# spectral_clock.net
KiCad netlist of a schematic drawn in Altium Designer
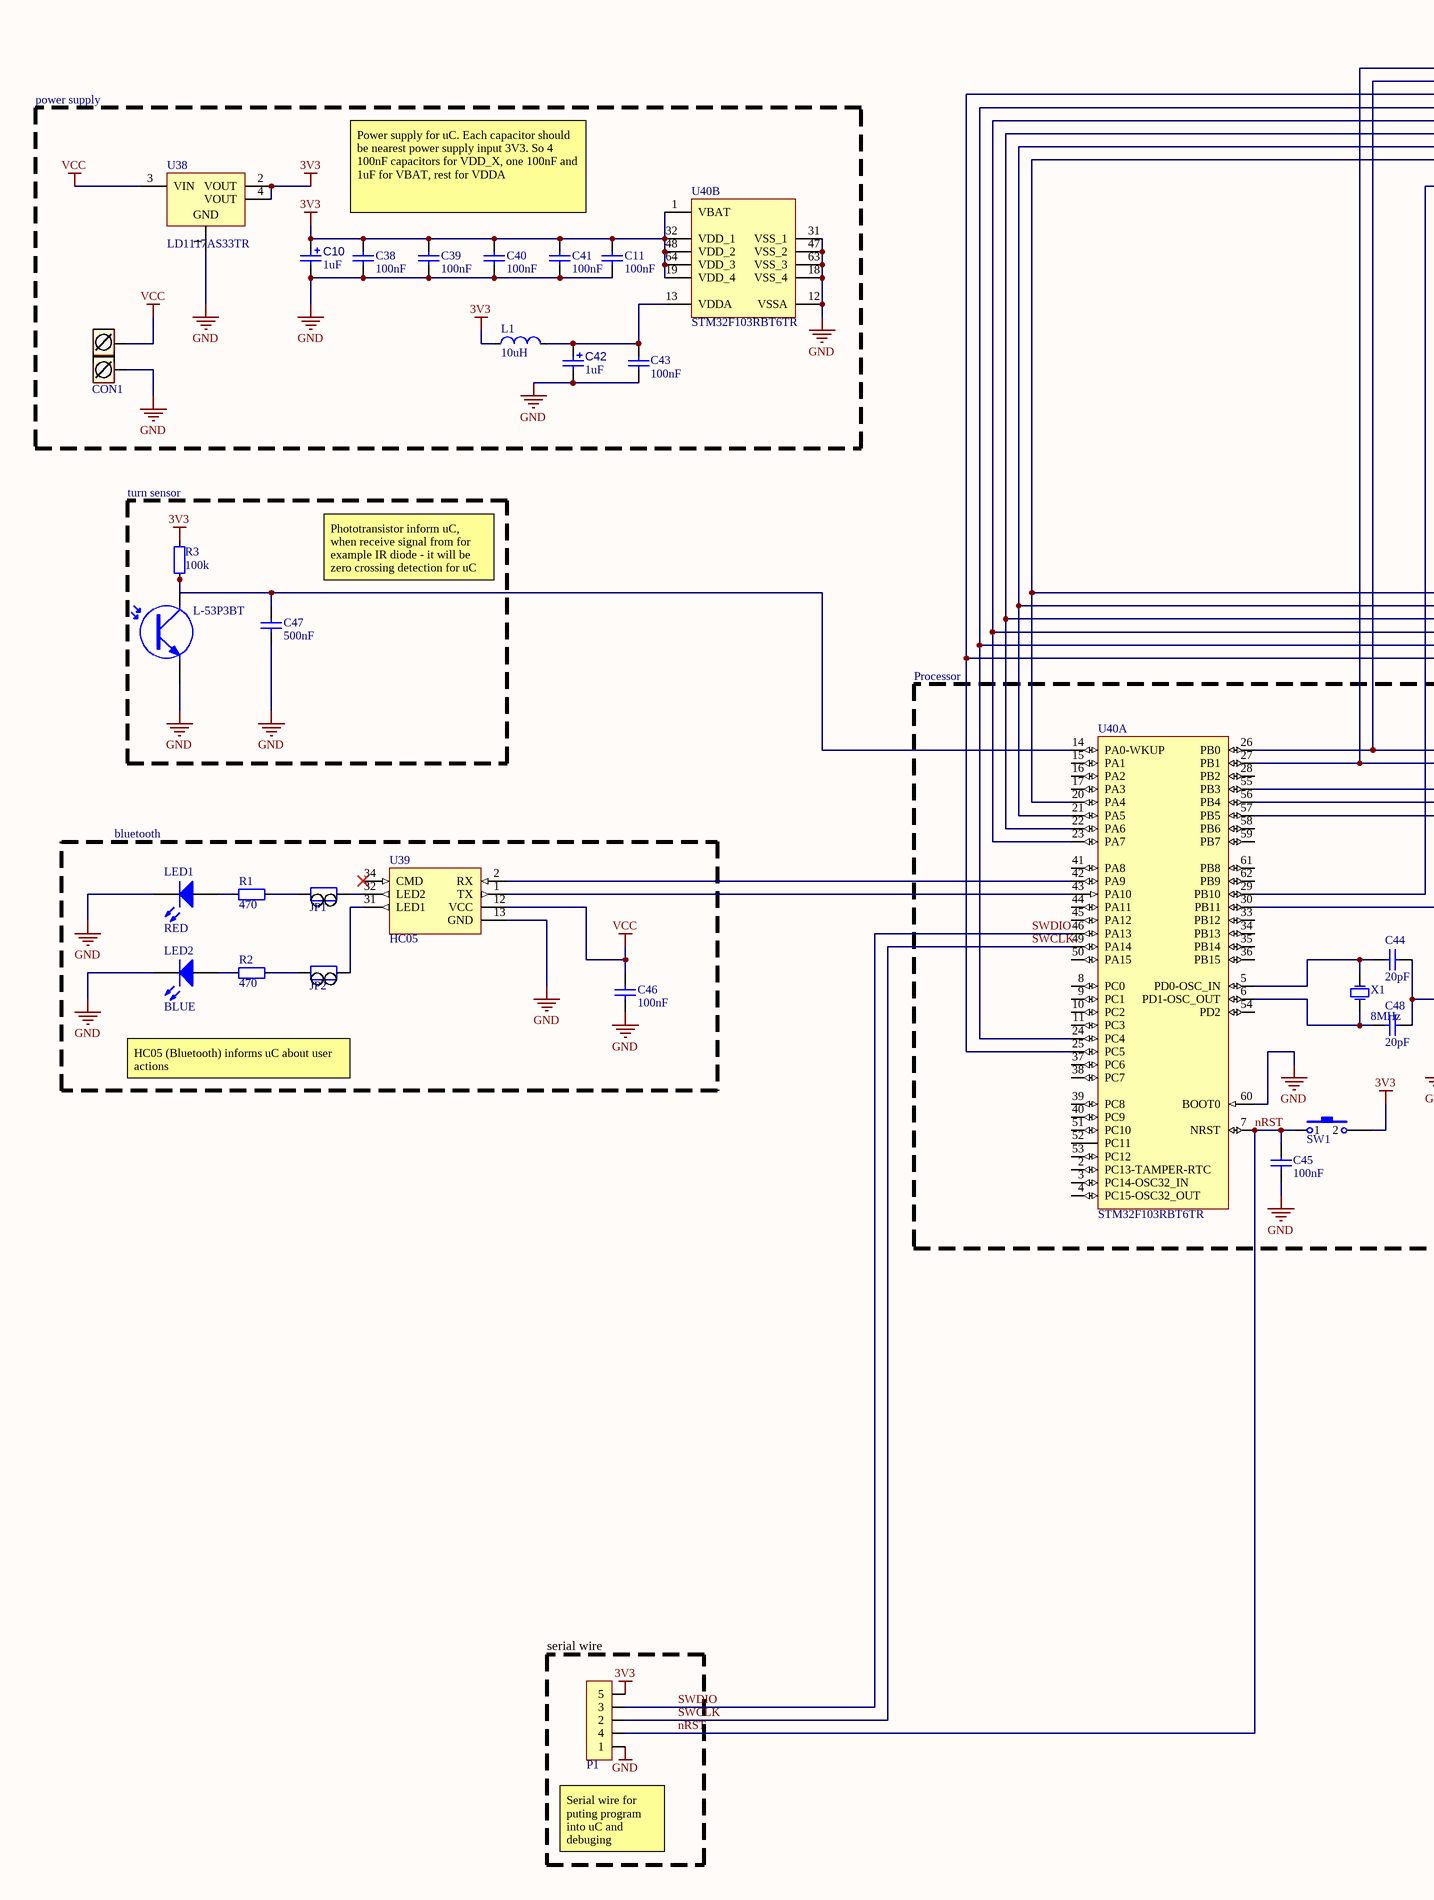
[diagram p0: spectral_clock.SchDoc, left]
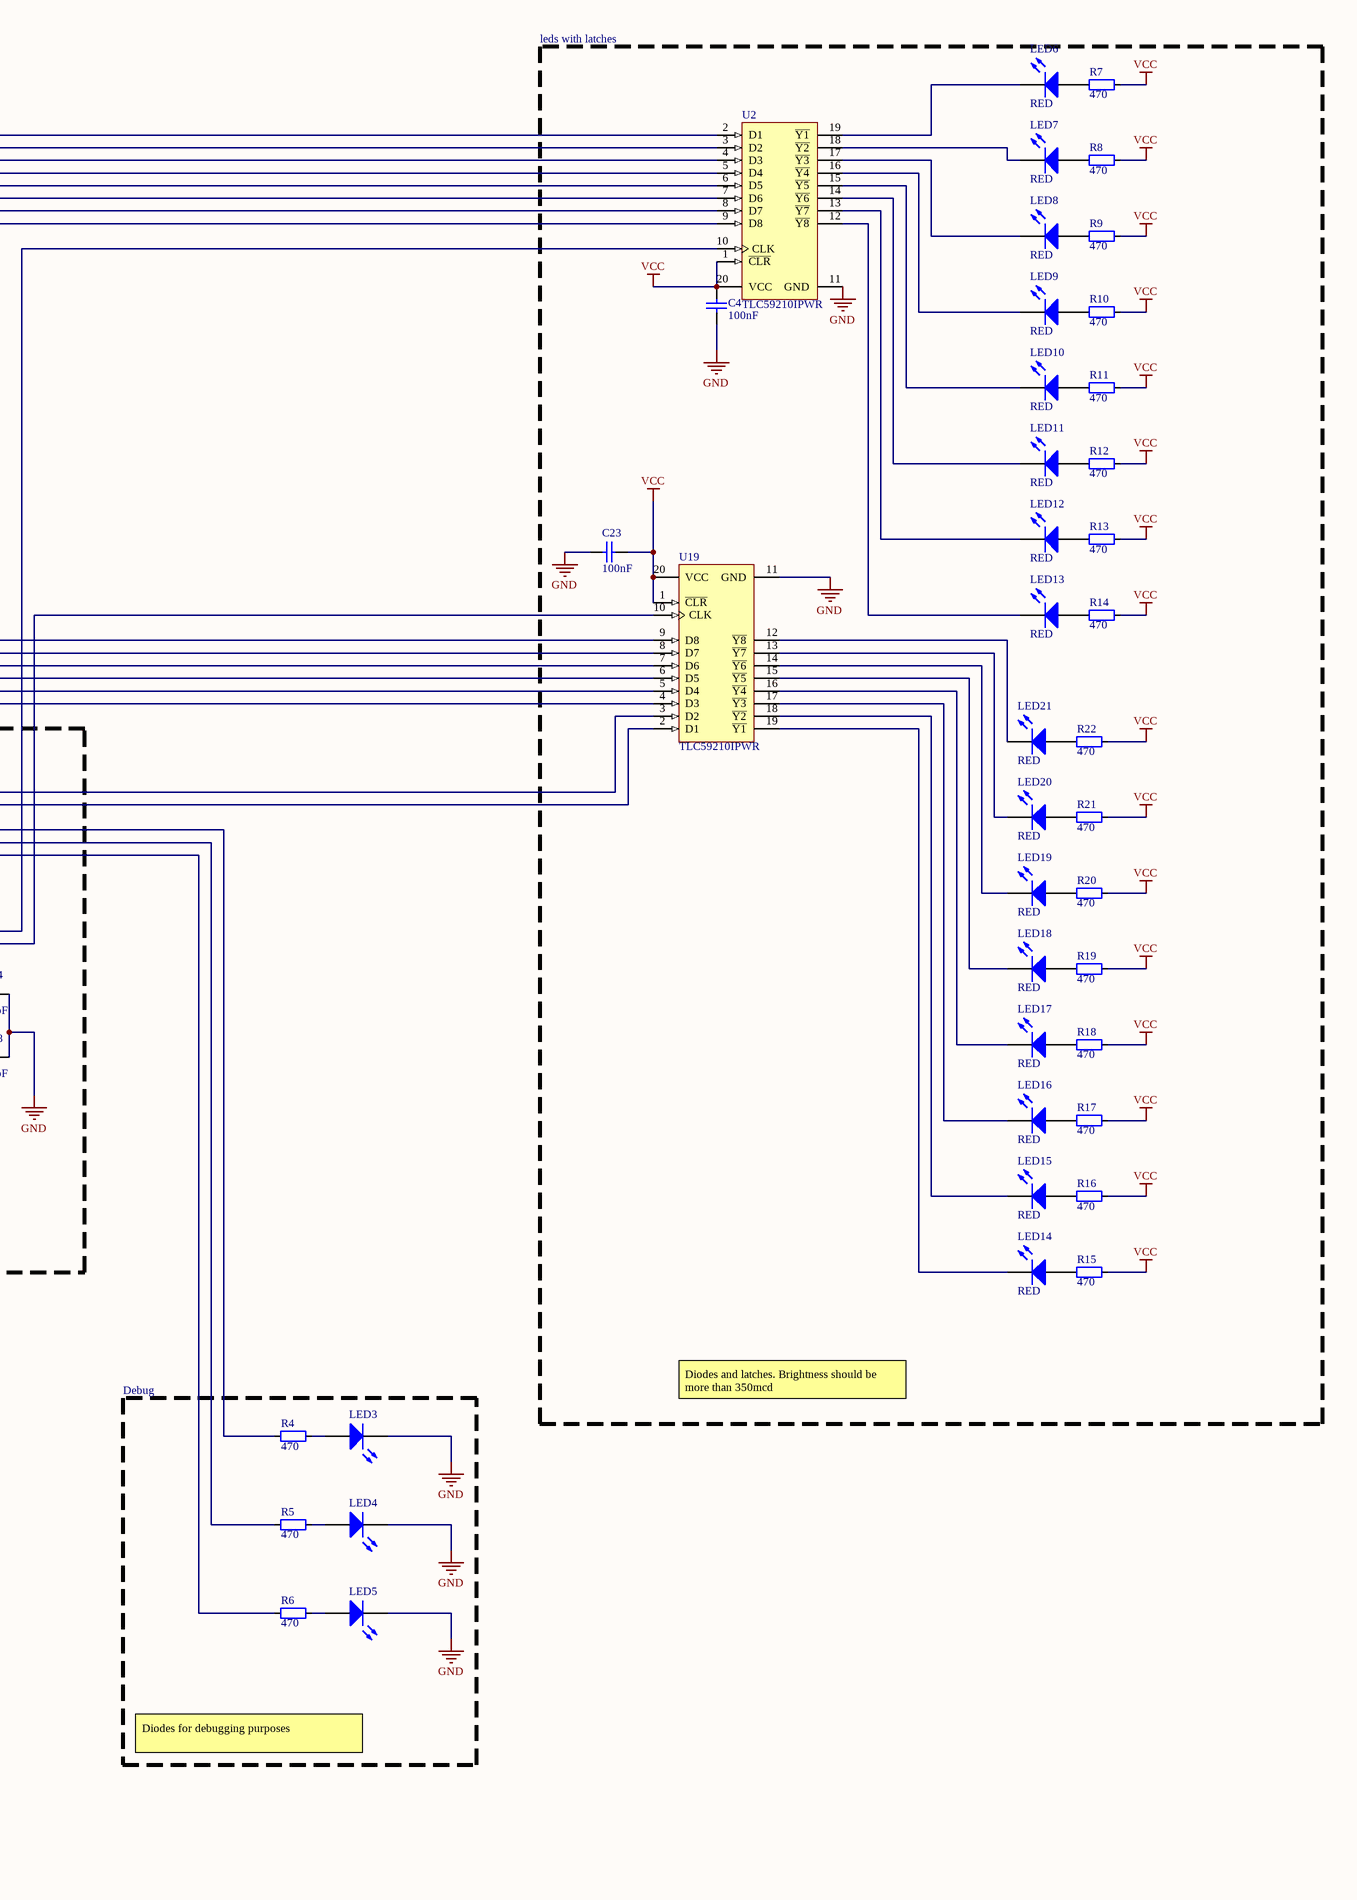
[diagram p1: spectral_clock.SchDoc, right]

(export (version "E")
  (design (tool "Eeschema 10.0.6"))
  (components
    (comp (ref "C4")
      (value "100nF")
      (footprint "0603_CAP")
      (description "Ceramic capacitor")
      (fields (field (name "Comment") "Cap"))
      (libsource (lib "Library_Altium") (part "Cap"))
    )
    (comp (ref "C10")
      (value "1uF")
      (footprint "Con_SMD_4x5")
      (description "Polar capacitor")
      (libsource (lib "altium_library_onyks") (part "Cap_Pol"))
    )
    (comp (ref "C11")
      (value "100nF")
      (footprint "0603_CAP")
      (description "Ceramic capacitor")
      (fields (field (name "Comment") "Cap"))
      (libsource (lib "altium_library_onyks") (part "Cap"))
    )
    (comp (ref "C23")
      (value "100nF")
      (footprint "0603_CAP")
      (description "Ceramic capacitor")
      (fields (field (name "Comment") "Cap"))
      (libsource (lib "Library_Altium") (part "Cap"))
    )
    (comp (ref "C38")
      (value "100nF")
      (footprint "0603_CAP")
      (description "Ceramic capacitor")
      (fields (field (name "Comment") "Cap"))
      (libsource (lib "altium_library_onyks") (part "Cap"))
    )
    (comp (ref "C39")
      (value "100nF")
      (footprint "0603_CAP")
      (description "Ceramic capacitor")
      (fields (field (name "Comment") "Cap"))
      (libsource (lib "altium_library_onyks") (part "Cap"))
    )
    (comp (ref "C40")
      (value "100nF")
      (footprint "0603_CAP")
      (description "Ceramic capacitor")
      (fields (field (name "Comment") "Cap"))
      (libsource (lib "altium_library_onyks") (part "Cap"))
    )
    (comp (ref "C41")
      (value "100nF")
      (footprint "0603_CAP")
      (description "Ceramic capacitor")
      (fields (field (name "Comment") "Cap"))
      (libsource (lib "altium_library_onyks") (part "Cap"))
    )
    (comp (ref "C42")
      (value "1uF")
      (footprint "Con_SMD_4x5")
      (description "Polar capacitor")
      (libsource (lib "altium_library_onyks") (part "Cap_Pol"))
    )
    (comp (ref "C43")
      (value "100nF")
      (footprint "0603_CAP")
      (description "Ceramic capacitor")
      (fields (field (name "Comment") "Cap"))
      (libsource (lib "altium_library_onyks") (part "Cap"))
    )
    (comp (ref "C44")
      (value "20pF")
      (footprint "0603_CAP")
      (description "Ceramic capacitor")
      (fields (field (name "Comment") "Cap"))
      (libsource (lib "Library_Altium") (part "Cap"))
    )
    (comp (ref "C45")
      (value "100nF")
      (footprint "0603_CAP")
      (description "Ceramic capacitor")
      (fields (field (name "Comment") "Cap"))
      (libsource (lib "altium_library_onyks") (part "Cap"))
    )
    (comp (ref "C46")
      (value "100nF")
      (footprint "0603_CAP")
      (description "Ceramic capacitor")
      (fields (field (name "Comment") "Cap"))
      (libsource (lib "Library_Altium") (part "Cap"))
    )
    (comp (ref "C47")
      (value "500nF")
      (footprint "0603_CAP")
      (description "Ceramic capacitor")
      (fields (field (name "Comment") "Cap"))
      (libsource (lib "altium_library_onyks") (part "Cap"))
    )
    (comp (ref "C48")
      (value "20pF")
      (footprint "0603_CAP")
      (description "Ceramic capacitor")
      (fields (field (name "Comment") "Cap"))
      (libsource (lib "Library_Altium") (part "Cap"))
    )
    (comp (ref "CON1")
      (value "ARK2")
      (footprint "ARK2")
      (description "Złącze śrubowe 2 piny")
      (libsource (lib "altium_library_onyks") (part "ARK2"))
    )
    (comp (ref "JP1")
      (value "Jumper")
      (footprint "HDR1X2 - JP")
      (description "Jumper, 2-Pin")
      (libsource (lib "altium_library_onyks") (part "Jumper_2"))
    )
    (comp (ref "JP2")
      (value "Jumper")
      (footprint "HDR1X2 - JP")
      (description "Jumper, 2-Pin")
      (libsource (lib "altium_library_onyks") (part "Jumper_2"))
    )
    (comp (ref "L-53P3BT")
      (value "Phototransistor")
      (footprint "LED_THT")
      (libsource (lib "altium_library_onyks") (part "Phototransistor"))
    )
    (comp (ref "L1")
      (value "10uH")
      (footprint "0603_IND")
      (fields (field (name "PUBLISHER") "Altium Limited"))
      (libsource (lib "altium_library_onyks") (part "Inductor"))
    )
    (comp (ref "LED1")
      (value "RED")
      (footprint "0603_led_red")
      (description "Light-emitting diode")
      (libsource (lib "altium_library_onyks") (part "LED"))
    )
    (comp (ref "LED2")
      (value "BLUE")
      (footprint "0603_led_blue")
      (description "Light-emitting diode")
      (libsource (lib "altium_library_onyks") (part "LED"))
    )
    (comp (ref "LED3")
      (value "~")
      (footprint "0603_led_green")
      (description "Light-emitting diode")
      (libsource (lib "altium_library_onyks") (part "LED"))
    )
    (comp (ref "LED4")
      (value "RED")
      (footprint "0603_led_green")
      (description "Light-emitting diode")
      (libsource (lib "altium_library_onyks") (part "LED"))
    )
    (comp (ref "LED5")
      (value "RED")
      (footprint "0603_led_green")
      (description "Light-emitting diode")
      (libsource (lib "altium_library_onyks") (part "LED"))
    )
    (comp (ref "LED6")
      (value "RED")
      (footprint "0603_led_blue")
      (description "Light-emitting diode")
      (libsource (lib "altium_library_onyks") (part "LED"))
    )
    (comp (ref "LED7")
      (value "RED")
      (footprint "0603_led_blue")
      (description "Light-emitting diode")
      (libsource (lib "altium_library_onyks") (part "LED"))
    )
    (comp (ref "LED8")
      (value "RED")
      (footprint "0603_led_blue")
      (description "Light-emitting diode")
      (libsource (lib "altium_library_onyks") (part "LED"))
    )
    (comp (ref "LED9")
      (value "RED")
      (footprint "0603_led_blue")
      (description "Light-emitting diode")
      (libsource (lib "altium_library_onyks") (part "LED"))
    )
    (comp (ref "LED10")
      (value "RED")
      (footprint "0603_led_blue")
      (description "Light-emitting diode")
      (libsource (lib "altium_library_onyks") (part "LED"))
    )
    (comp (ref "LED11")
      (value "RED")
      (footprint "0603_led_blue")
      (description "Light-emitting diode")
      (libsource (lib "altium_library_onyks") (part "LED"))
    )
    (comp (ref "LED12")
      (value "RED")
      (footprint "0603_led_blue")
      (description "Light-emitting diode")
      (libsource (lib "altium_library_onyks") (part "LED"))
    )
    (comp (ref "LED13")
      (value "RED")
      (footprint "0603_led_blue")
      (description "Light-emitting diode")
      (libsource (lib "altium_library_onyks") (part "LED"))
    )
    (comp (ref "LED14")
      (value "RED")
      (footprint "0603_led_blue")
      (description "Light-emitting diode")
      (libsource (lib "altium_library_onyks") (part "LED"))
    )
    (comp (ref "LED15")
      (value "RED")
      (footprint "0603_led_blue")
      (description "Light-emitting diode")
      (libsource (lib "altium_library_onyks") (part "LED"))
    )
    (comp (ref "LED16")
      (value "RED")
      (footprint "0603_led_blue")
      (description "Light-emitting diode")
      (libsource (lib "altium_library_onyks") (part "LED"))
    )
    (comp (ref "LED17")
      (value "RED")
      (footprint "0603_led_blue")
      (description "Light-emitting diode")
      (libsource (lib "altium_library_onyks") (part "LED"))
    )
    (comp (ref "LED18")
      (value "RED")
      (footprint "0603_led_blue")
      (description "Light-emitting diode")
      (libsource (lib "altium_library_onyks") (part "LED"))
    )
    (comp (ref "LED19")
      (value "RED")
      (footprint "0603_led_blue")
      (description "Light-emitting diode")
      (libsource (lib "altium_library_onyks") (part "LED"))
    )
    (comp (ref "LED20")
      (value "RED")
      (footprint "0603_led_blue")
      (description "Light-emitting diode")
      (libsource (lib "altium_library_onyks") (part "LED"))
    )
    (comp (ref "LED21")
      (value "RED")
      (footprint "0603_led_blue")
      (description "Light-emitting diode")
      (libsource (lib "altium_library_onyks") (part "LED"))
    )
    (comp (ref "P1")
      (value "HDR1X5")
      (footprint "HDR1X5")
      (description "Header, 5-Pin")
      (fields (field (name "PUBLISHER") "Altium Limited"))
      (libsource (lib "altium_library_onyks") (part "HDR1X5"))
    )
    (comp (ref "R1")
      (value "470")
      (footprint "0603_RES")
      (description "Resistior")
      (libsource (lib "") (part "RES_1"))
    )
    (comp (ref "R2")
      (value "470")
      (footprint "0603_RES")
      (description "Resistior")
      (libsource (lib "") (part "RES_1"))
    )
    (comp (ref "R3")
      (value "100k")
      (footprint "0603_RES")
      (description "Resistior")
      (libsource (lib "") (part "RES_2"))
    )
    (comp (ref "R4")
      (value "470")
      (footprint "0603_RES")
      (description "Resistior")
      (libsource (lib "altium_library_onyks") (part "RES"))
    )
    (comp (ref "R5")
      (value "470")
      (footprint "0603_RES")
      (description "Resistior")
      (libsource (lib "altium_library_onyks") (part "RES"))
    )
    (comp (ref "R6")
      (value "470")
      (footprint "0603_RES")
      (description "Resistior")
      (libsource (lib "altium_library_onyks") (part "RES"))
    )
    (comp (ref "R7")
      (value "470")
      (footprint "0603_RES")
      (description "Resistior")
      (libsource (lib "altium_library_onyks") (part "RES"))
    )
    (comp (ref "R8")
      (value "470")
      (footprint "0603_RES")
      (description "Resistior")
      (libsource (lib "altium_library_onyks") (part "RES"))
    )
    (comp (ref "R9")
      (value "470")
      (footprint "0603_RES")
      (description "Resistior")
      (libsource (lib "altium_library_onyks") (part "RES"))
    )
    (comp (ref "R10")
      (value "470")
      (footprint "0603_RES")
      (description "Resistior")
      (libsource (lib "altium_library_onyks") (part "RES"))
    )
    (comp (ref "R11")
      (value "470")
      (footprint "0603_RES")
      (description "Resistior")
      (libsource (lib "altium_library_onyks") (part "RES"))
    )
    (comp (ref "R12")
      (value "470")
      (footprint "0603_RES")
      (description "Resistior")
      (libsource (lib "altium_library_onyks") (part "RES"))
    )
    (comp (ref "R13")
      (value "470")
      (footprint "0603_RES")
      (description "Resistior")
      (libsource (lib "altium_library_onyks") (part "RES"))
    )
    (comp (ref "R14")
      (value "470")
      (footprint "0603_RES")
      (description "Resistior")
      (libsource (lib "altium_library_onyks") (part "RES"))
    )
    (comp (ref "R15")
      (value "470")
      (footprint "0603_RES")
      (description "Resistior")
      (libsource (lib "altium_library_onyks") (part "RES"))
    )
    (comp (ref "R16")
      (value "470")
      (footprint "0603_RES")
      (description "Resistior")
      (libsource (lib "altium_library_onyks") (part "RES"))
    )
    (comp (ref "R17")
      (value "470")
      (footprint "0603_RES")
      (description "Resistior")
      (libsource (lib "altium_library_onyks") (part "RES"))
    )
    (comp (ref "R18")
      (value "470")
      (footprint "0603_RES")
      (description "Resistior")
      (libsource (lib "altium_library_onyks") (part "RES"))
    )
    (comp (ref "R19")
      (value "470")
      (footprint "0603_RES")
      (description "Resistior")
      (libsource (lib "altium_library_onyks") (part "RES"))
    )
    (comp (ref "R20")
      (value "470")
      (footprint "0603_RES")
      (description "Resistior")
      (libsource (lib "altium_library_onyks") (part "RES"))
    )
    (comp (ref "R21")
      (value "470")
      (footprint "0603_RES")
      (description "Resistior")
      (libsource (lib "altium_library_onyks") (part "RES"))
    )
    (comp (ref "R22")
      (value "470")
      (footprint "0603_RES")
      (description "Resistior")
      (libsource (lib "altium_library_onyks") (part "RES"))
    )
    (comp (ref "SW1")
      (value "Micro_Switch")
      (footprint "Tact 34N-F")
      (description "Switch")
      (fields (field (name "PUBLISHER") "Altium Limited"))
      (libsource (lib "altium_library_onyks") (part "Micro_Switch"))
    )
    (comp (ref "U2")
      (value "TLC59210IPWR")
      (footprint "PW0020A_M")
      (fields (field (name "MANUFACTURER") "Texas Instruments"))
      (libsource (lib "Altium Content Vault") (part "TI-TLC5921X-20"))
    )
    (comp (ref "U19")
      (value "TLC59210IPWR")
      (footprint "PW0020A_M")
      (fields (field (name "MANUFACTURER") "Texas Instruments"))
      (libsource (lib "") (part "TI-TLC5921X-20_1"))
    )
    (comp (ref "U38")
      (value "LD1117AS33TR")
      (footprint "SOT-223_M")
      (description "1A, Low Drop Positive Voltage Regulator, 3.3V, 4-Pin SOT-223, Tape and Reel")
      (libsource (lib "Altium Content Vault") (part "PM-REG-LD1117-SOT4"))
    )
    (comp (ref "U39")
      (value "HC05")
      (footprint "HC05")
      (description "Bluetooth to Serial Port Module")
      (libsource (lib "altium_library_onyks") (part "HC05"))
    )
    (comp (ref "U40")
      (value "STM32F103RBT6TR")
      (footprint "STM-LQFP64_V")
      (libsource (lib "Altium Content Vault") (part "MC-ARM-STM32F103X8_B-SQ64"))
    )
    (comp (ref "X1")
      (value "8MHz")
      (footprint "HC49/4H_SMX")
      (description "Oscillator")
      (libsource (lib "altium_library_onyks") (part "XTAL"))
    )
  )
  (nets
    (net (code "1") (name "/SWCLK") (class "Default")
      (node (ref "P1") (pin "2") (pinfunction "2_2") (pintype "passive"))
      (node (ref "U40") (pin "49") (pinfunction "PA14_49") (pintype "bidirectional"))
    )
    (net (code "2") (name "/SWDIO") (class "Default")
      (node (ref "P1") (pin "3") (pinfunction "3_3") (pintype "passive"))
      (node (ref "U40") (pin "46") (pinfunction "PA13_46") (pintype "bidirectional"))
    )
    (net (code "3") (name "/nRST") (class "Default")
      (node (ref "C45") (pin "2") (pinfunction "2_2") (pintype "passive"))
      (node (ref "P1") (pin "4") (pinfunction "4_4") (pintype "passive"))
      (node (ref "SW1") (pin "1") (pinfunction "1_1") (pintype "passive"))
      (node (ref "U40") (pin "7") (pinfunction "NRST_7") (pintype "bidirectional"))
    )
    (net (code "4") (name "3V3") (class "Default")
      (node (ref "C10") (pin "1") (pinfunction "1_1") (pintype "passive"))
      (node (ref "C11") (pin "2") (pinfunction "2_2") (pintype "passive"))
      (node (ref "C38") (pin "2") (pinfunction "2_2") (pintype "passive"))
      (node (ref "C39") (pin "2") (pinfunction "2_2") (pintype "passive"))
      (node (ref "C40") (pin "2") (pinfunction "2_2") (pintype "passive"))
      (node (ref "C41") (pin "2") (pinfunction "2_2") (pintype "passive"))
      (node (ref "L1") (pin "1") (pinfunction "1_1") (pintype "passive"))
      (node (ref "P1") (pin "5") (pinfunction "5_5") (pintype "passive"))
      (node (ref "R3") (pin "2") (pinfunction "2_2") (pintype "passive"))
      (node (ref "SW1") (pin "2") (pinfunction "2_2") (pintype "passive"))
      (node (ref "U38") (pin "2") (pinfunction "VOUT_2") (pintype "power_in"))
      (node (ref "U38") (pin "4") (pinfunction "VOUT_4") (pintype "power_in"))
      (node (ref "U40") (pin "1") (pinfunction "VBAT_1") (pintype "power_in"))
      (node (ref "U40") (pin "19") (pinfunction "VDD_4_19") (pintype "power_in"))
      (node (ref "U40") (pin "32") (pinfunction "VDD_1_32") (pintype "power_in"))
      (node (ref "U40") (pin "48") (pinfunction "VDD_2_48") (pintype "power_in"))
      (node (ref "U40") (pin "64") (pinfunction "VDD_3_64") (pintype "power_in"))
    )
    (net (code "5") (name "GND") (class "Default")
      (node (ref "C10") (pin "2") (pinfunction "2_2") (pintype "passive"))
      (node (ref "C11") (pin "1") (pinfunction "1_1") (pintype "passive"))
      (node (ref "C23") (pin "2") (pinfunction "2_2") (pintype "passive"))
      (node (ref "C38") (pin "1") (pinfunction "1_1") (pintype "passive"))
      (node (ref "C39") (pin "1") (pinfunction "1_1") (pintype "passive"))
      (node (ref "C4") (pin "2") (pinfunction "2_2") (pintype "passive"))
      (node (ref "C40") (pin "1") (pinfunction "1_1") (pintype "passive"))
      (node (ref "C41") (pin "1") (pinfunction "1_1") (pintype "passive"))
      (node (ref "C42") (pin "2") (pinfunction "2_2") (pintype "passive"))
      (node (ref "C43") (pin "1") (pinfunction "1_1") (pintype "passive"))
      (node (ref "C44") (pin "2") (pinfunction "2_2") (pintype "passive"))
      (node (ref "C45") (pin "1") (pinfunction "1_1") (pintype "passive"))
      (node (ref "C46") (pin "2") (pinfunction "2_2") (pintype "passive"))
      (node (ref "C47") (pin "1") (pinfunction "1_1") (pintype "passive"))
      (node (ref "C48") (pin "2") (pinfunction "2_2") (pintype "passive"))
      (node (ref "CON1") (pin "1") (pinfunction "1_1") (pintype "passive"))
      (node (ref "L-53P3BT") (pin "1") (pinfunction "E_1") (pintype "passive"))
      (node (ref "LED1") (pin "2") (pinfunction "K_2") (pintype "passive"))
      (node (ref "LED2") (pin "2") (pinfunction "K_2") (pintype "passive"))
      (node (ref "LED3") (pin "2") (pinfunction "K_2") (pintype "passive"))
      (node (ref "LED4") (pin "2") (pinfunction "K_2") (pintype "passive"))
      (node (ref "LED5") (pin "2") (pinfunction "K_2") (pintype "passive"))
      (node (ref "P1") (pin "1") (pinfunction "1_1") (pintype "passive"))
      (node (ref "U19") (pin "11") (pinfunction "GND_11") (pintype "power_in"))
      (node (ref "U2") (pin "11") (pinfunction "GND_11") (pintype "power_in"))
      (node (ref "U38") (pin "1") (pinfunction "GND_1") (pintype "power_in"))
      (node (ref "U39") (pin "13") (pinfunction "GND_13") (pintype "power_in"))
      (node (ref "U40") (pin "12") (pinfunction "VSSA_12") (pintype "power_in"))
      (node (ref "U40") (pin "18") (pinfunction "VSS_4_18") (pintype "power_in"))
      (node (ref "U40") (pin "31") (pinfunction "VSS_1_31") (pintype "power_in"))
      (node (ref "U40") (pin "47") (pinfunction "VSS_2_47") (pintype "power_in"))
      (node (ref "U40") (pin "60") (pinfunction "BOOT0_60") (pintype "input"))
      (node (ref "U40") (pin "63") (pinfunction "VSS_3_63") (pintype "power_in"))
    )
    (net (code "6") (name "Net-(JP1-Pad2)") (class "Default")
      (node (ref "JP1") (pin "2") (pinfunction "2_2") (pintype "passive"))
      (node (ref "R1") (pin "1") (pinfunction "1_1") (pintype "passive"))
    )
    (net (code "7") (name "Net-(JP2-Pad2)") (class "Default")
      (node (ref "JP2") (pin "2") (pinfunction "2_2") (pintype "passive"))
      (node (ref "R2") (pin "1") (pinfunction "1_1") (pintype "passive"))
    )
    (net (code "8") (name "Net-(L-53P3BT-C)") (class "Default")
      (node (ref "C47") (pin "2") (pinfunction "2_2") (pintype "passive"))
      (node (ref "L-53P3BT") (pin "2") (pinfunction "C_2") (pintype "passive"))
      (node (ref "R3") (pin "1") (pinfunction "1_1") (pintype "passive"))
      (node (ref "U40") (pin "14") (pinfunction "PA0-WKUP_14") (pintype "bidirectional"))
    )
    (net (code "9") (name "Net-(LED1-A)") (class "Default")
      (node (ref "LED1") (pin "1") (pinfunction "A_1") (pintype "passive"))
      (node (ref "R1") (pin "2") (pinfunction "2_2") (pintype "passive"))
    )
    (net (code "10") (name "Net-(LED2-A)") (class "Default")
      (node (ref "LED2") (pin "1") (pinfunction "A_1") (pintype "passive"))
      (node (ref "R2") (pin "2") (pinfunction "2_2") (pintype "passive"))
    )
    (net (code "11") (name "Net-(LED3-A)") (class "Default")
      (node (ref "LED3") (pin "1") (pinfunction "A_1") (pintype "passive"))
      (node (ref "R4") (pin "2") (pinfunction "2_2") (pintype "passive"))
    )
    (net (code "12") (name "Net-(LED4-A)") (class "Default")
      (node (ref "LED4") (pin "1") (pinfunction "A_1") (pintype "passive"))
      (node (ref "R5") (pin "2") (pinfunction "2_2") (pintype "passive"))
    )
    (net (code "13") (name "Net-(LED5-A)") (class "Default")
      (node (ref "LED5") (pin "1") (pinfunction "A_1") (pintype "passive"))
      (node (ref "R6") (pin "2") (pinfunction "2_2") (pintype "passive"))
    )
    (net (code "14") (name "Net-(LED6-A)") (class "Default")
      (node (ref "LED6") (pin "1") (pinfunction "A_1") (pintype "passive"))
      (node (ref "R7") (pin "1") (pinfunction "1_1") (pintype "passive"))
    )
    (net (code "15") (name "Net-(LED6-K)") (class "Default")
      (node (ref "LED6") (pin "2") (pinfunction "K_2") (pintype "passive"))
      (node (ref "U2") (pin "19") (pinfunction "~{Y1}_19") (pintype "open_collector"))
    )
    (net (code "16") (name "Net-(LED7-A)") (class "Default")
      (node (ref "LED7") (pin "1") (pinfunction "A_1") (pintype "passive"))
      (node (ref "R8") (pin "1") (pinfunction "1_1") (pintype "passive"))
    )
    (net (code "17") (name "Net-(LED7-K)") (class "Default")
      (node (ref "LED7") (pin "2") (pinfunction "K_2") (pintype "passive"))
      (node (ref "U2") (pin "18") (pinfunction "~{Y2}_18") (pintype "open_collector"))
    )
    (net (code "18") (name "Net-(LED8-A)") (class "Default")
      (node (ref "LED8") (pin "1") (pinfunction "A_1") (pintype "passive"))
      (node (ref "R9") (pin "1") (pinfunction "1_1") (pintype "passive"))
    )
    (net (code "19") (name "Net-(LED8-K)") (class "Default")
      (node (ref "LED8") (pin "2") (pinfunction "K_2") (pintype "passive"))
      (node (ref "U2") (pin "17") (pinfunction "~{Y3}_17") (pintype "open_collector"))
    )
    (net (code "20") (name "Net-(LED9-A)") (class "Default")
      (node (ref "LED9") (pin "1") (pinfunction "A_1") (pintype "passive"))
      (node (ref "R10") (pin "1") (pinfunction "1_1") (pintype "passive"))
    )
    (net (code "21") (name "Net-(LED9-K)") (class "Default")
      (node (ref "LED9") (pin "2") (pinfunction "K_2") (pintype "passive"))
      (node (ref "U2") (pin "16") (pinfunction "~{Y4}_16") (pintype "open_collector"))
    )
    (net (code "22") (name "Net-(LED10-A)") (class "Default")
      (node (ref "LED10") (pin "1") (pinfunction "A_1") (pintype "passive"))
      (node (ref "R11") (pin "1") (pinfunction "1_1") (pintype "passive"))
    )
    (net (code "23") (name "Net-(LED10-K)") (class "Default")
      (node (ref "LED10") (pin "2") (pinfunction "K_2") (pintype "passive"))
      (node (ref "U2") (pin "15") (pinfunction "~{Y5}_15") (pintype "open_collector"))
    )
    (net (code "24") (name "Net-(LED11-A)") (class "Default")
      (node (ref "LED11") (pin "1") (pinfunction "A_1") (pintype "passive"))
      (node (ref "R12") (pin "1") (pinfunction "1_1") (pintype "passive"))
    )
    (net (code "25") (name "Net-(LED11-K)") (class "Default")
      (node (ref "LED11") (pin "2") (pinfunction "K_2") (pintype "passive"))
      (node (ref "U2") (pin "14") (pinfunction "~{Y6}_14") (pintype "open_collector"))
    )
    (net (code "26") (name "Net-(LED12-A)") (class "Default")
      (node (ref "LED12") (pin "1") (pinfunction "A_1") (pintype "passive"))
      (node (ref "R13") (pin "1") (pinfunction "1_1") (pintype "passive"))
    )
    (net (code "27") (name "Net-(LED12-K)") (class "Default")
      (node (ref "LED12") (pin "2") (pinfunction "K_2") (pintype "passive"))
      (node (ref "U2") (pin "13") (pinfunction "~{Y7}_13") (pintype "open_collector"))
    )
    (net (code "28") (name "Net-(LED13-A)") (class "Default")
      (node (ref "LED13") (pin "1") (pinfunction "A_1") (pintype "passive"))
      (node (ref "R14") (pin "1") (pinfunction "1_1") (pintype "passive"))
    )
    (net (code "29") (name "Net-(LED13-K)") (class "Default")
      (node (ref "LED13") (pin "2") (pinfunction "K_2") (pintype "passive"))
      (node (ref "U2") (pin "12") (pinfunction "~{Y8}_12") (pintype "open_collector"))
    )
    (net (code "30") (name "Net-(LED14-A)") (class "Default")
      (node (ref "LED14") (pin "1") (pinfunction "A_1") (pintype "passive"))
      (node (ref "R15") (pin "1") (pinfunction "1_1") (pintype "passive"))
    )
    (net (code "31") (name "Net-(LED14-K)") (class "Default")
      (node (ref "LED14") (pin "2") (pinfunction "K_2") (pintype "passive"))
      (node (ref "U19") (pin "19") (pinfunction "~{Y1}_19") (pintype "open_collector"))
    )
    (net (code "32") (name "Net-(LED15-A)") (class "Default")
      (node (ref "LED15") (pin "1") (pinfunction "A_1") (pintype "passive"))
      (node (ref "R16") (pin "1") (pinfunction "1_1") (pintype "passive"))
    )
    (net (code "33") (name "Net-(LED15-K)") (class "Default")
      (node (ref "LED15") (pin "2") (pinfunction "K_2") (pintype "passive"))
      (node (ref "U19") (pin "18") (pinfunction "~{Y2}_18") (pintype "open_collector"))
    )
    (net (code "34") (name "Net-(LED16-A)") (class "Default")
      (node (ref "LED16") (pin "1") (pinfunction "A_1") (pintype "passive"))
      (node (ref "R17") (pin "1") (pinfunction "1_1") (pintype "passive"))
    )
    (net (code "35") (name "Net-(LED16-K)") (class "Default")
      (node (ref "LED16") (pin "2") (pinfunction "K_2") (pintype "passive"))
      (node (ref "U19") (pin "17") (pinfunction "~{Y3}_17") (pintype "open_collector"))
    )
    (net (code "36") (name "Net-(LED17-A)") (class "Default")
      (node (ref "LED17") (pin "1") (pinfunction "A_1") (pintype "passive"))
      (node (ref "R18") (pin "1") (pinfunction "1_1") (pintype "passive"))
    )
    (net (code "37") (name "Net-(LED17-K)") (class "Default")
      (node (ref "LED17") (pin "2") (pinfunction "K_2") (pintype "passive"))
      (node (ref "U19") (pin "16") (pinfunction "~{Y4}_16") (pintype "open_collector"))
    )
    (net (code "38") (name "Net-(LED18-A)") (class "Default")
      (node (ref "LED18") (pin "1") (pinfunction "A_1") (pintype "passive"))
      (node (ref "R19") (pin "1") (pinfunction "1_1") (pintype "passive"))
    )
    (net (code "39") (name "Net-(LED18-K)") (class "Default")
      (node (ref "LED18") (pin "2") (pinfunction "K_2") (pintype "passive"))
      (node (ref "U19") (pin "15") (pinfunction "~{Y5}_15") (pintype "open_collector"))
    )
    (net (code "40") (name "Net-(LED19-A)") (class "Default")
      (node (ref "LED19") (pin "1") (pinfunction "A_1") (pintype "passive"))
      (node (ref "R20") (pin "1") (pinfunction "1_1") (pintype "passive"))
    )
    (net (code "41") (name "Net-(LED19-K)") (class "Default")
      (node (ref "LED19") (pin "2") (pinfunction "K_2") (pintype "passive"))
      (node (ref "U19") (pin "14") (pinfunction "~{Y6}_14") (pintype "open_collector"))
    )
    (net (code "42") (name "Net-(LED20-A)") (class "Default")
      (node (ref "LED20") (pin "1") (pinfunction "A_1") (pintype "passive"))
      (node (ref "R21") (pin "1") (pinfunction "1_1") (pintype "passive"))
    )
    (net (code "43") (name "Net-(LED20-K)") (class "Default")
      (node (ref "LED20") (pin "2") (pinfunction "K_2") (pintype "passive"))
      (node (ref "U19") (pin "13") (pinfunction "~{Y7}_13") (pintype "open_collector"))
    )
    (net (code "44") (name "Net-(LED21-A)") (class "Default")
      (node (ref "LED21") (pin "1") (pinfunction "A_1") (pintype "passive"))
      (node (ref "R22") (pin "1") (pinfunction "1_1") (pintype "passive"))
    )
    (net (code "45") (name "Net-(LED21-K)") (class "Default")
      (node (ref "LED21") (pin "2") (pinfunction "K_2") (pintype "passive"))
      (node (ref "U19") (pin "12") (pinfunction "~{Y8}_12") (pintype "open_collector"))
    )
    (net (code "46") (name "Net-(U2-CLK)") (class "Default")
      (node (ref "U2") (pin "10") (pinfunction "CLK_10") (pintype "input"))
      (node (ref "U40") (pin "29") (pinfunction "PB10_29") (pintype "bidirectional"))
    )
    (net (code "47") (name "Net-(U19-CLK)") (class "Default")
      (node (ref "U19") (pin "10") (pinfunction "CLK_10") (pintype "input"))
      (node (ref "U40") (pin "30") (pinfunction "PB11_30") (pintype "bidirectional"))
    )
    (net (code "48") (name "Net-(U19-D1)") (class "Default")
      (node (ref "U19") (pin "2") (pinfunction "D1_2") (pintype "input"))
      (node (ref "U2") (pin "2") (pinfunction "D1_2") (pintype "input"))
      (node (ref "U40") (pin "27") (pinfunction "PB1_27") (pintype "bidirectional"))
    )
    (net (code "49") (name "Net-(U19-D2)") (class "Default")
      (node (ref "U19") (pin "3") (pinfunction "D2_3") (pintype "input"))
      (node (ref "U2") (pin "3") (pinfunction "D2_3") (pintype "input"))
      (node (ref "U40") (pin "26") (pinfunction "PB0_26") (pintype "bidirectional"))
    )
    (net (code "50") (name "Net-(U19-D3)") (class "Default")
      (node (ref "U19") (pin "4") (pinfunction "D3_4") (pintype "input"))
      (node (ref "U2") (pin "4") (pinfunction "D3_4") (pintype "input"))
      (node (ref "U40") (pin "25") (pinfunction "PC5_25") (pintype "bidirectional"))
    )
    (net (code "51") (name "Net-(U19-D4)") (class "Default")
      (node (ref "U19") (pin "5") (pinfunction "D4_5") (pintype "input"))
      (node (ref "U2") (pin "5") (pinfunction "D4_5") (pintype "input"))
      (node (ref "U40") (pin "24") (pinfunction "PC4_24") (pintype "bidirectional"))
    )
    (net (code "52") (name "Net-(U19-D5)") (class "Default")
      (node (ref "U19") (pin "6") (pinfunction "D5_6") (pintype "input"))
      (node (ref "U2") (pin "6") (pinfunction "D5_6") (pintype "input"))
      (node (ref "U40") (pin "23") (pinfunction "PA7_23") (pintype "bidirectional"))
    )
    (net (code "53") (name "Net-(U19-D6)") (class "Default")
      (node (ref "U19") (pin "7") (pinfunction "D6_7") (pintype "input"))
      (node (ref "U2") (pin "7") (pinfunction "D6_7") (pintype "input"))
      (node (ref "U40") (pin "22") (pinfunction "PA6_22") (pintype "bidirectional"))
    )
    (net (code "54") (name "Net-(U19-D7)") (class "Default")
      (node (ref "U19") (pin "8") (pinfunction "D7_8") (pintype "input"))
      (node (ref "U2") (pin "8") (pinfunction "D7_8") (pintype "input"))
      (node (ref "U40") (pin "21") (pinfunction "PA5_21") (pintype "bidirectional"))
    )
    (net (code "55") (name "Net-(U19-D8)") (class "Default")
      (node (ref "U19") (pin "9") (pinfunction "D8_9") (pintype "input"))
      (node (ref "U2") (pin "9") (pinfunction "D8_9") (pintype "input"))
      (node (ref "U40") (pin "20") (pinfunction "PA4_20") (pintype "bidirectional"))
    )
    (net (code "56") (name "Net-(U39-LED1)") (class "Default")
      (node (ref "JP2") (pin "1") (pinfunction "1_1") (pintype "passive"))
      (node (ref "U39") (pin "31") (pinfunction "LED1_31") (pintype "output"))
    )
    (net (code "57") (name "Net-(U39-LED2)") (class "Default")
      (node (ref "JP1") (pin "1") (pinfunction "1_1") (pintype "passive"))
      (node (ref "U39") (pin "32") (pinfunction "LED2_32") (pintype "output"))
    )
    (net (code "58") (name "Net-(U39-RX)") (class "Default")
      (node (ref "U39") (pin "2") (pinfunction "RX_2") (pintype "input"))
      (node (ref "U40") (pin "42") (pinfunction "PA9_42") (pintype "bidirectional"))
    )
    (net (code "59") (name "Net-(U39-TX)") (class "Default")
      (node (ref "U39") (pin "1") (pinfunction "TX_1") (pintype "output"))
      (node (ref "U40") (pin "43") (pinfunction "PA10_43") (pintype "bidirectional"))
    )
    (net (code "60") (name "Net-(U40A-PB3)") (class "Default")
      (node (ref "R4") (pin "1") (pinfunction "1_1") (pintype "passive"))
      (node (ref "U40") (pin "55") (pinfunction "PB3_55") (pintype "bidirectional"))
    )
    (net (code "61") (name "Net-(U40A-PB4)") (class "Default")
      (node (ref "R5") (pin "1") (pinfunction "1_1") (pintype "passive"))
      (node (ref "U40") (pin "56") (pinfunction "PB4_56") (pintype "bidirectional"))
    )
    (net (code "62") (name "Net-(U40A-PB5)") (class "Default")
      (node (ref "R6") (pin "1") (pinfunction "1_1") (pintype "passive"))
      (node (ref "U40") (pin "57") (pinfunction "PB5_57") (pintype "bidirectional"))
    )
    (net (code "63") (name "Net-(U40A-PD0-OSC_IN)") (class "Default")
      (node (ref "C44") (pin "1") (pinfunction "1_1") (pintype "passive"))
      (node (ref "U40") (pin "5") (pinfunction "PD0-OSC_IN_5") (pintype "bidirectional"))
      (node (ref "X1") (pin "1") (pinfunction "OSC1_1") (pintype "passive"))
    )
    (net (code "64") (name "Net-(U40A-PD1-OSC_OUT)") (class "Default")
      (node (ref "C48") (pin "1") (pinfunction "1_1") (pintype "passive"))
      (node (ref "U40") (pin "6") (pinfunction "PD1-OSC_OUT_6") (pintype "bidirectional"))
      (node (ref "X1") (pin "2") (pinfunction "OSC2_2") (pintype "passive"))
    )
    (net (code "65") (name "Net-(U40B-VDDA)") (class "Default")
      (node (ref "C42") (pin "1") (pinfunction "1_1") (pintype "passive"))
      (node (ref "C43") (pin "2") (pinfunction "2_2") (pintype "passive"))
      (node (ref "L1") (pin "2") (pinfunction "2_2") (pintype "passive"))
      (node (ref "U40") (pin "13") (pinfunction "VDDA_13") (pintype "power_in"))
    )
    (net (code "66") (name "VCC") (class "Default")
      (node (ref "C23") (pin "1") (pinfunction "1_1") (pintype "passive"))
      (node (ref "C4") (pin "1") (pinfunction "1_1") (pintype "passive"))
      (node (ref "C46") (pin "1") (pinfunction "1_1") (pintype "passive"))
      (node (ref "CON1") (pin "2") (pinfunction "2_2") (pintype "passive"))
      (node (ref "R10") (pin "2") (pinfunction "2_2") (pintype "passive"))
      (node (ref "R11") (pin "2") (pinfunction "2_2") (pintype "passive"))
      (node (ref "R12") (pin "2") (pinfunction "2_2") (pintype "passive"))
      (node (ref "R13") (pin "2") (pinfunction "2_2") (pintype "passive"))
      (node (ref "R14") (pin "2") (pinfunction "2_2") (pintype "passive"))
      (node (ref "R15") (pin "2") (pinfunction "2_2") (pintype "passive"))
      (node (ref "R16") (pin "2") (pinfunction "2_2") (pintype "passive"))
      (node (ref "R17") (pin "2") (pinfunction "2_2") (pintype "passive"))
      (node (ref "R18") (pin "2") (pinfunction "2_2") (pintype "passive"))
      (node (ref "R19") (pin "2") (pinfunction "2_2") (pintype "passive"))
      (node (ref "R20") (pin "2") (pinfunction "2_2") (pintype "passive"))
      (node (ref "R21") (pin "2") (pinfunction "2_2") (pintype "passive"))
      (node (ref "R22") (pin "2") (pinfunction "2_2") (pintype "passive"))
      (node (ref "R7") (pin "2") (pinfunction "2_2") (pintype "passive"))
      (node (ref "R8") (pin "2") (pinfunction "2_2") (pintype "passive"))
      (node (ref "R9") (pin "2") (pinfunction "2_2") (pintype "passive"))
      (node (ref "U19") (pin "1") (pinfunction "~{CLR}_1") (pintype "input"))
      (node (ref "U19") (pin "20") (pinfunction "VCC_20") (pintype "power_in"))
      (node (ref "U2") (pin "1") (pinfunction "~{CLR}_1") (pintype "input"))
      (node (ref "U2") (pin "20") (pinfunction "VCC_20") (pintype "power_in"))
      (node (ref "U38") (pin "3") (pinfunction "VIN_3") (pintype "power_in"))
      (node (ref "U39") (pin "12") (pinfunction "VCC_12") (pintype "power_in"))
    )
    (net (code "67") (name "unconnected-(U39-CMD-Pad34)") (class "Default")
      (node (ref "U39") (pin "34") (pinfunction "CMD_34") (pintype "input+no_connect"))
    )
    (net (code "68") (name "unconnected-(U40A-PA1-Pad15)") (class "Default")
      (node (ref "U40") (pin "15") (pinfunction "PA1_15") (pintype "bidirectional"))
    )
    (net (code "69") (name "unconnected-(U40A-PA2-Pad16)") (class "Default")
      (node (ref "U40") (pin "16") (pinfunction "PA2_16") (pintype "bidirectional"))
    )
    (net (code "70") (name "unconnected-(U40A-PA3-Pad17)") (class "Default")
      (node (ref "U40") (pin "17") (pinfunction "PA3_17") (pintype "bidirectional"))
    )
    (net (code "71") (name "unconnected-(U40A-PA8-Pad41)") (class "Default")
      (node (ref "U40") (pin "41") (pinfunction "PA8_41") (pintype "bidirectional"))
    )
    (net (code "72") (name "unconnected-(U40A-PA11-Pad44)") (class "Default")
      (node (ref "U40") (pin "44") (pinfunction "PA11_44") (pintype "bidirectional"))
    )
    (net (code "73") (name "unconnected-(U40A-PA12-Pad45)") (class "Default")
      (node (ref "U40") (pin "45") (pinfunction "PA12_45") (pintype "bidirectional"))
    )
    (net (code "74") (name "unconnected-(U40A-PA15-Pad50)") (class "Default")
      (node (ref "U40") (pin "50") (pinfunction "PA15_50") (pintype "bidirectional"))
    )
    (net (code "75") (name "unconnected-(U40A-PB2-Pad28)") (class "Default")
      (node (ref "U40") (pin "28") (pinfunction "PB2_28") (pintype "bidirectional"))
    )
    (net (code "76") (name "unconnected-(U40A-PB6-Pad58)") (class "Default")
      (node (ref "U40") (pin "58") (pinfunction "PB6_58") (pintype "bidirectional"))
    )
    (net (code "77") (name "unconnected-(U40A-PB7-Pad59)") (class "Default")
      (node (ref "U40") (pin "59") (pinfunction "PB7_59") (pintype "bidirectional"))
    )
    (net (code "78") (name "unconnected-(U40A-PB8-Pad61)") (class "Default")
      (node (ref "U40") (pin "61") (pinfunction "PB8_61") (pintype "bidirectional"))
    )
    (net (code "79") (name "unconnected-(U40A-PB9-Pad62)") (class "Default")
      (node (ref "U40") (pin "62") (pinfunction "PB9_62") (pintype "bidirectional"))
    )
    (net (code "80") (name "unconnected-(U40A-PB12-Pad33)") (class "Default")
      (node (ref "U40") (pin "33") (pinfunction "PB12_33") (pintype "bidirectional"))
    )
    (net (code "81") (name "unconnected-(U40A-PB13-Pad34)") (class "Default")
      (node (ref "U40") (pin "34") (pinfunction "PB13_34") (pintype "bidirectional"))
    )
    (net (code "82") (name "unconnected-(U40A-PB14-Pad35)") (class "Default")
      (node (ref "U40") (pin "35") (pinfunction "PB14_35") (pintype "bidirectional"))
    )
    (net (code "83") (name "unconnected-(U40A-PB15-Pad36)") (class "Default")
      (node (ref "U40") (pin "36") (pinfunction "PB15_36") (pintype "bidirectional"))
    )
    (net (code "84") (name "unconnected-(U40A-PC0-Pad8)") (class "Default")
      (node (ref "U40") (pin "8") (pinfunction "PC0_8") (pintype "bidirectional"))
    )
    (net (code "85") (name "unconnected-(U40A-PC1-Pad9)") (class "Default")
      (node (ref "U40") (pin "9") (pinfunction "PC1_9") (pintype "bidirectional"))
    )
    (net (code "86") (name "unconnected-(U40A-PC2-Pad10)") (class "Default")
      (node (ref "U40") (pin "10") (pinfunction "PC2_10") (pintype "bidirectional"))
    )
    (net (code "87") (name "unconnected-(U40A-PC3-Pad11)") (class "Default")
      (node (ref "U40") (pin "11") (pinfunction "PC3_11") (pintype "bidirectional"))
    )
    (net (code "88") (name "unconnected-(U40A-PC6-Pad37)") (class "Default")
      (node (ref "U40") (pin "37") (pinfunction "PC6_37") (pintype "bidirectional"))
    )
    (net (code "89") (name "unconnected-(U40A-PC7-Pad38)") (class "Default")
      (node (ref "U40") (pin "38") (pinfunction "PC7_38") (pintype "bidirectional"))
    )
    (net (code "90") (name "unconnected-(U40A-PC8-Pad39)") (class "Default")
      (node (ref "U40") (pin "39") (pinfunction "PC8_39") (pintype "bidirectional"))
    )
    (net (code "91") (name "unconnected-(U40A-PC9-Pad40)") (class "Default")
      (node (ref "U40") (pin "40") (pinfunction "PC9_40") (pintype "bidirectional"))
    )
    (net (code "92") (name "unconnected-(U40A-PC10-Pad51)") (class "Default")
      (node (ref "U40") (pin "51") (pinfunction "PC10_51") (pintype "bidirectional"))
    )
    (net (code "93") (name "unconnected-(U40A-PC11-Pad52)") (class "Default")
      (node (ref "U40") (pin "52") (pinfunction "PC11_52") (pintype "bidirectional"))
    )
    (net (code "94") (name "unconnected-(U40A-PC12-Pad53)") (class "Default")
      (node (ref "U40") (pin "53") (pinfunction "PC12_53") (pintype "bidirectional"))
    )
    (net (code "95") (name "unconnected-(U40A-PC13-TAMPER-RTC-Pad2)") (class "Default")
      (node (ref "U40") (pin "2") (pinfunction "PC13-TAMPER-RTC_2") (pintype "bidirectional"))
    )
    (net (code "96") (name "unconnected-(U40A-PC14-OSC32_IN-Pad3)") (class "Default")
      (node (ref "U40") (pin "3") (pinfunction "PC14-OSC32_IN_3") (pintype "bidirectional"))
    )
    (net (code "97") (name "unconnected-(U40A-PC15-OSC32_OUT-Pad4)") (class "Default")
      (node (ref "U40") (pin "4") (pinfunction "PC15-OSC32_OUT_4") (pintype "bidirectional"))
    )
    (net (code "98") (name "unconnected-(U40A-PD2-Pad54)") (class "Default")
      (node (ref "U40") (pin "54") (pinfunction "PD2_54") (pintype "bidirectional"))
    )
  )
)
